# Audio_Output.net
KiCad netlist of a schematic drawn in Altium Designer
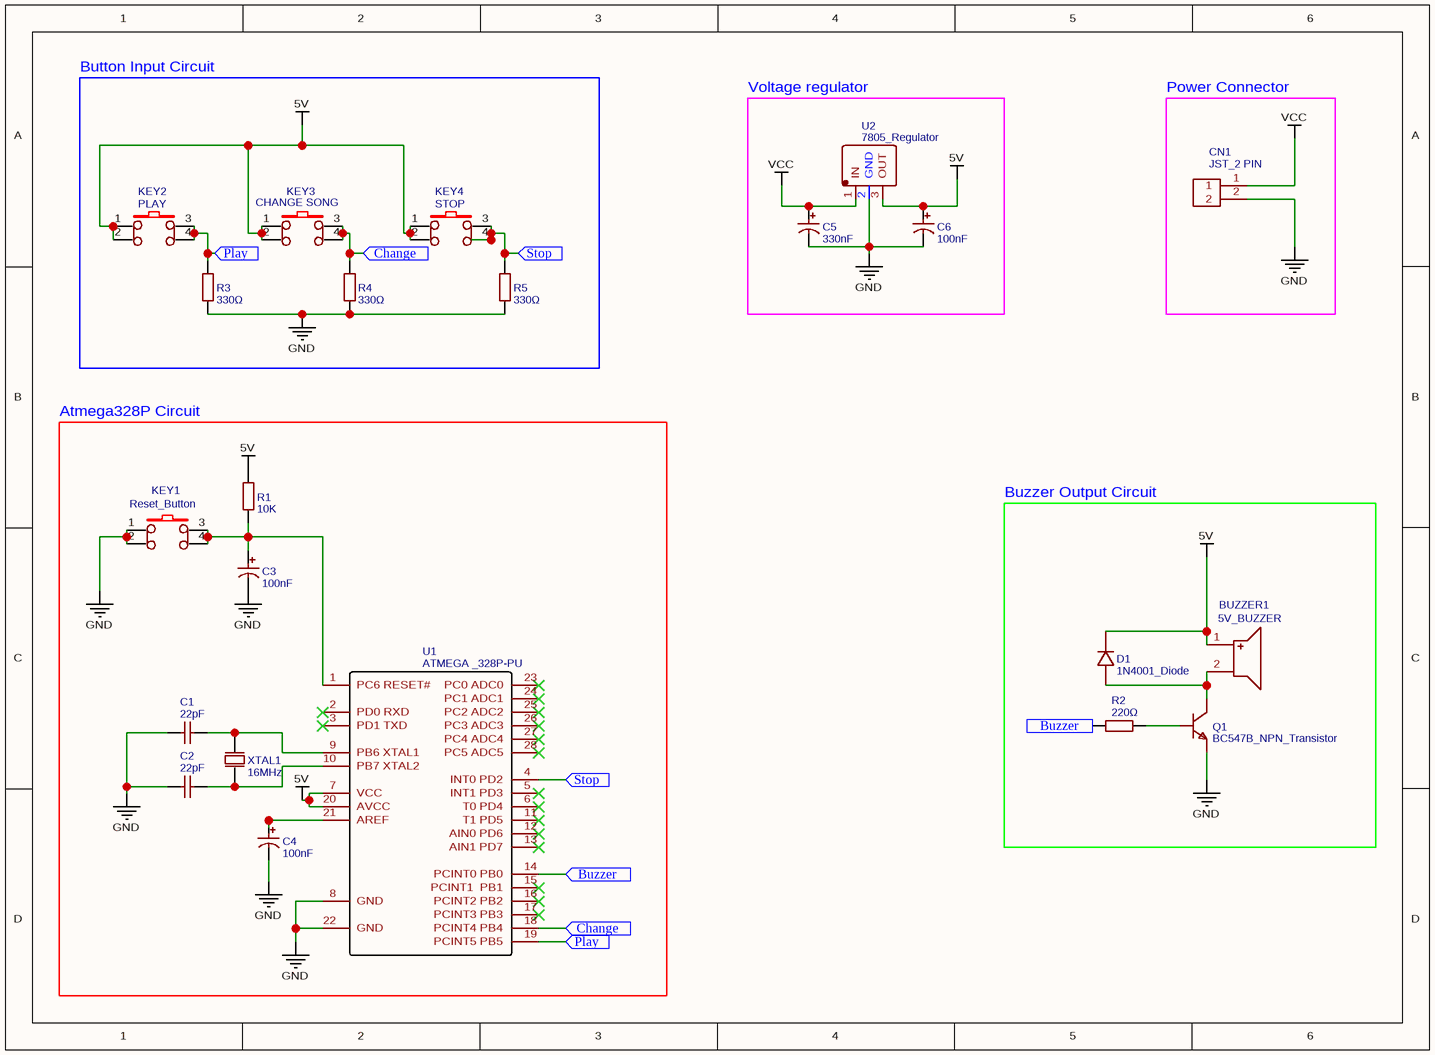
[diagram p0: Audio Output.schdoc]

(export (version "E")
  (design (tool "Eeschema 10.0.6"))
  (components
    (comp (ref "BUZZER1")
      (value "5V_BUZZER")
      (fields
        (field (name "BOM_MANUFACTURER PART") "BUZZERHMB1206-03")
        (field (name "BOM_SUPPLIER PART") "C96101")
        (field (name "CONTRIBUTOR") "วริศรา เกรียงไกรวัฒน์ /ทิพพะ")
      )
      (libsource (lib "altium-import") (part "root_0_5V_BUZZER_"))
    )
    (comp (ref "C1")
      (value "22pF")
      (fields
        (field (name "BOM_MANUFACTURER PART") "22pf/50V 10%")
        (field (name "BOM_SUPPLIER PART") "C9316")
      )
      (libsource (lib "altium-import") (part "root_0_22pF_"))
    )
    (comp (ref "C2")
      (value "22pF")
      (fields
        (field (name "BOM_MANUFACTURER PART") "22pf/50V 10%")
        (field (name "BOM_SUPPLIER PART") "C9316")
      )
      (libsource (lib "altium-import") (part "root_0_22pF_"))
    )
    (comp (ref "C3")
      (value "100nF")
      (fields (field (name "BOM_MANUFACTURER PART") "0.1UF 50V") (field (name "BOM_SUPPLIER PART") "C28061"))
      (libsource (lib "altium-import") (part "root_0_100nF_"))
    )
    (comp (ref "C4")
      (value "100nF")
      (fields (field (name "BOM_MANUFACTURER PART") "0.1UF 50V") (field (name "BOM_SUPPLIER PART") "C28061"))
      (libsource (lib "altium-import") (part "root_0_100nF_"))
    )
    (comp (ref "C5")
      (value "330nF")
      (fields
        (field (name "BOM_MANUFACTURER PART") "0.33uF 50V 5*11")
        (field (name "BOM_SUPPLIER PART") "C45097")
      )
      (libsource (lib "altium-import") (part "root_0_330nF_"))
    )
    (comp (ref "C6")
      (value "100nF")
      (fields (field (name "BOM_MANUFACTURER PART") "0.1UF 50V") (field (name "BOM_SUPPLIER PART") "C28061"))
      (libsource (lib "altium-import") (part "root_0_100nF_"))
    )
    (comp (ref "CN1")
      (value "JST_2 PIN")
      (fields
        (field (name "BOM_MANUFACTURER PART") "XHB-2A Connector")
        (field (name "BOM_SUPPLIER PART") "C57981")
      )
      (libsource (lib "altium-import") (part "root_0_JST_2 PIN_"))
    )
    (comp (ref "D1")
      (value "1N4001_Diode")
      (fields
        (field (name "BOM_SUPPLIER PART") "C99656")
        (field (name "BOM_MANUFACTURER PART") "1N4001-T")
        (field (name "CONTRIBUTOR") "LCSC")
      )
      (libsource (lib "altium-import") (part "root_3_1N4001_Diode_"))
    )
    (comp (ref "KEY1")
      (value "Reset_Button")
      (fields
        (field (name "BOM_SUPPLIER PART") "C59980")
        (field (name "BOM_MANUFACTURER PART") "button6*6*8.5")
      )
      (libsource (lib "altium-import") (part "root_0_Reset_Button_"))
    )
    (comp (ref "KEY2")
      (value "PLAY")
      (fields
        (field (name "BOM_SUPPLIER PART") "C59980")
        (field (name "BOM_MANUFACTURER PART") "button6*6*8.5")
      )
      (libsource (lib "altium-import") (part "root_0_PLAY_"))
    )
    (comp (ref "KEY3")
      (value "CHANGE SONG")
      (fields
        (field (name "BOM_SUPPLIER PART") "C59980")
        (field (name "BOM_MANUFACTURER PART") "button6*6*8.5")
      )
      (libsource (lib "altium-import") (part "root_0_CHANGE SONG_"))
    )
    (comp (ref "KEY4")
      (value "STOP")
      (fields
        (field (name "BOM_SUPPLIER PART") "C59980")
        (field (name "BOM_MANUFACTURER PART") "button6*6*8.5")
      )
      (libsource (lib "altium-import") (part "root_0_STOP_"))
    )
    (comp (ref "Q1")
      (value "BC547B_NPN_Transistor")
      (fields
        (field (name "BOM_SUPPLIER PART") "C713613")
        (field (name "BOM_MANUFACTURER PART") "BC547B")
        (field (name "CONTRIBUTOR") "LCSC")
      )
      (libsource (lib "altium-import") (part "root_0_BC547B_NPN_Transistor_"))
    )
    (comp (ref "R1")
      (value "10K")
      (fields
        (field (name "POWER") "1/4W")
        (field (name "TOLERANCE") "±1%")
        (field (name "BOM_SUPPLIER PART") "E57439")
      )
      (libsource (lib "altium-import") (part "root_1_10K_"))
    )
    (comp (ref "R2")
      (value "220Ω")
      (fields
        (field (name "POWER") "1/4W")
        (field (name "TOLERANCE") "±1%")
        (field (name "BOM_SUPPLIER PART") "E57439")
      )
      (libsource (lib "altium-import") (part "root_0_220Ω_"))
    )
    (comp (ref "R3")
      (value "330Ω")
      (fields
        (field (name "POWER") "1/4W")
        (field (name "TOLERANCE") "±1%")
        (field (name "BOM_SUPPLIER PART") "E57439")
      )
      (libsource (lib "altium-import") (part "root_1_330Ω_"))
    )
    (comp (ref "R4")
      (value "330Ω")
      (fields
        (field (name "POWER") "1/4W")
        (field (name "TOLERANCE") "±1%")
        (field (name "BOM_SUPPLIER PART") "E57439")
      )
      (libsource (lib "altium-import") (part "root_1_330Ω_"))
    )
    (comp (ref "R5")
      (value "330Ω")
      (fields
        (field (name "POWER") "1/4W")
        (field (name "TOLERANCE") "±1%")
        (field (name "BOM_SUPPLIER PART") "E57439")
      )
      (libsource (lib "altium-import") (part "root_1_330Ω_"))
    )
    (comp (ref "U1")
      (value "ATMEGA _328P-PU")
      (fields
        (field (name "BOM_MANUFACTURER PART") "ATMEGA328P-PU")
        (field (name "BOM_SUPPLIER PART") "C33901")
        (field (name "CONTRIBUTOR") "LCSC")
      )
      (libsource (lib "altium-import") (part "root_0_ATMEGA _328P-PU_"))
    )
    (comp (ref "U2")
      (value "7805_Regulator")
      (fields
        (field (name "BOM_SUPPLIER PART") "C305416")
        (field (name "BOM_MANUFACTURER PART") "7805")
        (field (name "CONTRIBUTOR") "LCSC")
      )
      (libsource (lib "altium-import") (part "root_1_7805_Regulator_"))
    )
    (comp (ref "XTAL1")
      (value "16MHz")
      (fields
        (field (name "BOM_MANUFACTURER PART") "0SC-16MHz")
        (field (name "CONTRIBUTOR") "Mantas Petrauskas")
      )
      (libsource (lib "altium-import") (part "root_1_16MHz_"))
    )
  )
  (nets
    (net (code "1") (name "/Buzzer") (class "Default")
      (node (ref "R2") (pin "1") (pinfunction "1_1") (pintype "passive"))
      (node (ref "U1") (pin "14") (pinfunction "PCINT0_PB0_14") (pintype "passive"))
    )
    (net (code "2") (name "/Change") (class "Default")
      (node (ref "KEY3") (pin "3") (pinfunction "3_3") (pintype "passive"))
      (node (ref "KEY3") (pin "4") (pinfunction "4_4") (pintype "passive"))
      (node (ref "R4") (pin "2") (pinfunction "2_2") (pintype "passive"))
      (node (ref "U1") (pin "18") (pinfunction "PCINT4_PB4_18") (pintype "passive"))
    )
    (net (code "3") (name "/Play") (class "Default")
      (node (ref "KEY2") (pin "3") (pinfunction "3_3") (pintype "passive"))
      (node (ref "KEY2") (pin "4") (pinfunction "4_4") (pintype "passive"))
      (node (ref "R3") (pin "2") (pinfunction "2_2") (pintype "passive"))
      (node (ref "U1") (pin "19") (pinfunction "PCINT5_PB5_19") (pintype "passive"))
    )
    (net (code "4") (name "/Stop") (class "Default")
      (node (ref "KEY4") (pin "3") (pinfunction "3_3") (pintype "passive"))
      (node (ref "KEY4") (pin "4") (pinfunction "4_4") (pintype "passive"))
      (node (ref "R5") (pin "2") (pinfunction "2_2") (pintype "passive"))
      (node (ref "U1") (pin "4") (pinfunction "INT0_PD2_4") (pintype "passive"))
    )
    (net (code "5") (name "5V") (class "Default")
      (node (ref "BUZZER1") (pin "1") (pinfunction "1_1") (pintype "passive"))
      (node (ref "C6") (pin "1") (pinfunction "1_1") (pintype "passive"))
      (node (ref "D1") (pin "1") (pinfunction "C_1") (pintype "passive"))
      (node (ref "KEY2") (pin "1") (pinfunction "1_1") (pintype "passive"))
      (node (ref "KEY2") (pin "2") (pinfunction "2_2") (pintype "passive"))
      (node (ref "KEY3") (pin "1") (pinfunction "1_1") (pintype "passive"))
      (node (ref "KEY3") (pin "2") (pinfunction "2_2") (pintype "passive"))
      (node (ref "KEY4") (pin "1") (pinfunction "1_1") (pintype "passive"))
      (node (ref "KEY4") (pin "2") (pinfunction "2_2") (pintype "passive"))
      (node (ref "R1") (pin "2") (pinfunction "2_2") (pintype "passive"))
      (node (ref "U1") (pin "20") (pinfunction "AVCC_20") (pintype "passive"))
      (node (ref "U1") (pin "7") (pinfunction "VCC_7") (pintype "passive"))
      (node (ref "U2") (pin "3") (pinfunction "OUT_3") (pintype "passive"))
    )
    (net (code "6") (name "GND") (class "Default")
      (node (ref "C1") (pin "1") (pinfunction "1_1") (pintype "passive"))
      (node (ref "C2") (pin "1") (pinfunction "1_1") (pintype "passive"))
      (node (ref "C3") (pin "2") (pinfunction "2_2") (pintype "passive"))
      (node (ref "C4") (pin "2") (pinfunction "2_2") (pintype "passive"))
      (node (ref "C5") (pin "2") (pinfunction "2_2") (pintype "passive"))
      (node (ref "C6") (pin "2") (pinfunction "2_2") (pintype "passive"))
      (node (ref "CN1") (pin "2") (pinfunction "2_2") (pintype "passive"))
      (node (ref "KEY1") (pin "1") (pinfunction "1_1") (pintype "passive"))
      (node (ref "KEY1") (pin "2") (pinfunction "2_2") (pintype "passive"))
      (node (ref "Q1") (pin "3") (pinfunction "E_3") (pintype "passive"))
      (node (ref "R3") (pin "1") (pinfunction "1_1") (pintype "passive"))
      (node (ref "R4") (pin "1") (pinfunction "1_1") (pintype "passive"))
      (node (ref "R5") (pin "1") (pinfunction "1_1") (pintype "passive"))
      (node (ref "U1") (pin "22") (pinfunction "GND_22") (pintype "passive"))
      (node (ref "U1") (pin "8") (pinfunction "GND_8") (pintype "passive"))
      (node (ref "U2") (pin "2") (pinfunction "GND_2") (pintype "passive"))
    )
    (net (code "7") (name "Net-(D1-A)") (class "Default")
      (node (ref "BUZZER1") (pin "2") (pinfunction "2_2") (pintype "passive"))
      (node (ref "D1") (pin "2") (pinfunction "A_2") (pintype "passive"))
      (node (ref "Q1") (pin "1") (pinfunction "C_1") (pintype "passive"))
    )
    (net (code "8") (name "Net-(Q1-B)") (class "Default")
      (node (ref "Q1") (pin "2") (pinfunction "B_2") (pintype "passive"))
      (node (ref "R2") (pin "2") (pinfunction "2_2") (pintype "passive"))
    )
    (net (code "9") (name "Net-(U1-AREF)") (class "Default")
      (node (ref "C4") (pin "1") (pinfunction "1_1") (pintype "passive"))
      (node (ref "U1") (pin "21") (pinfunction "AREF_21") (pintype "passive"))
    )
    (net (code "10") (name "Net-(U1-PB6_XTAL1)") (class "Default")
      (node (ref "C1") (pin "2") (pinfunction "2_2") (pintype "passive"))
      (node (ref "U1") (pin "9") (pinfunction "PB6_XTAL1_9") (pintype "passive"))
      (node (ref "XTAL1") (pin "1") (pinfunction "OSC1_1") (pintype "passive"))
    )
    (net (code "11") (name "Net-(U1-PB7_XTAL2)") (class "Default")
      (node (ref "C2") (pin "2") (pinfunction "2_2") (pintype "passive"))
      (node (ref "U1") (pin "10") (pinfunction "PB7_XTAL2_10") (pintype "passive"))
      (node (ref "XTAL1") (pin "2") (pinfunction "OSC2_2") (pintype "passive"))
    )
    (net (code "12") (name "Net-(U1-PC6_RESET#)") (class "Default")
      (node (ref "C3") (pin "1") (pinfunction "1_1") (pintype "passive"))
      (node (ref "KEY1") (pin "3") (pinfunction "3_3") (pintype "passive"))
      (node (ref "KEY1") (pin "4") (pinfunction "4_4") (pintype "passive"))
      (node (ref "R1") (pin "1") (pinfunction "1_1") (pintype "passive"))
      (node (ref "U1") (pin "1") (pinfunction "PC6_RESET#_1") (pintype "passive"))
    )
    (net (code "13") (name "VCC") (class "Default")
      (node (ref "C5") (pin "1") (pinfunction "1_1") (pintype "passive"))
      (node (ref "CN1") (pin "1") (pinfunction "1_1") (pintype "passive"))
      (node (ref "U2") (pin "1") (pinfunction "IN_1") (pintype "passive"))
    )
    (net (code "14") (name "unconnected-(U1-AIN0_PD6-Pad12)") (class "Default")
      (node (ref "U1") (pin "12") (pinfunction "AIN0_PD6_12") (pintype "passive+no_connect"))
    )
    (net (code "15") (name "unconnected-(U1-AIN1_PD7-Pad13)") (class "Default")
      (node (ref "U1") (pin "13") (pinfunction "AIN1_PD7_13") (pintype "passive+no_connect"))
    )
    (net (code "16") (name "unconnected-(U1-INT1_PD3-Pad5)") (class "Default")
      (node (ref "U1") (pin "5") (pinfunction "INT1_PD3_5") (pintype "passive+no_connect"))
    )
    (net (code "17") (name "unconnected-(U1-PC0_ADC0-Pad23)") (class "Default")
      (node (ref "U1") (pin "23") (pinfunction "PC0_ADC0_23") (pintype "passive+no_connect"))
    )
    (net (code "18") (name "unconnected-(U1-PC1_ADC1-Pad24)") (class "Default")
      (node (ref "U1") (pin "24") (pinfunction "PC1_ADC1_24") (pintype "passive+no_connect"))
    )
    (net (code "19") (name "unconnected-(U1-PC2_ADC2-Pad25)") (class "Default")
      (node (ref "U1") (pin "25") (pinfunction "PC2_ADC2_25") (pintype "passive+no_connect"))
    )
    (net (code "20") (name "unconnected-(U1-PC3_ADC3-Pad26)") (class "Default")
      (node (ref "U1") (pin "26") (pinfunction "PC3_ADC3_26") (pintype "passive+no_connect"))
    )
    (net (code "21") (name "unconnected-(U1-PC4_ADC4-Pad27)") (class "Default")
      (node (ref "U1") (pin "27") (pinfunction "PC4_ADC4_27") (pintype "passive+no_connect"))
    )
    (net (code "22") (name "unconnected-(U1-PC5_ADC5-Pad28)") (class "Default")
      (node (ref "U1") (pin "28") (pinfunction "PC5_ADC5_28") (pintype "passive+no_connect"))
    )
    (net (code "23") (name "unconnected-(U1-PCINT1__PB1-Pad15)") (class "Default")
      (node (ref "U1") (pin "15") (pinfunction "PCINT1__PB1_15") (pintype "passive+no_connect"))
    )
    (net (code "24") (name "unconnected-(U1-PCINT2_PB2-Pad16)") (class "Default")
      (node (ref "U1") (pin "16") (pinfunction "PCINT2_PB2_16") (pintype "passive+no_connect"))
    )
    (net (code "25") (name "unconnected-(U1-PCINT3_PB3-Pad17)") (class "Default")
      (node (ref "U1") (pin "17") (pinfunction "PCINT3_PB3_17") (pintype "passive+no_connect"))
    )
    (net (code "26") (name "unconnected-(U1-PD0_RXD-Pad2)") (class "Default")
      (node (ref "U1") (pin "2") (pinfunction "PD0_RXD_2") (pintype "passive+no_connect"))
    )
    (net (code "27") (name "unconnected-(U1-PD1_TXD-Pad3)") (class "Default")
      (node (ref "U1") (pin "3") (pinfunction "PD1_TXD_3") (pintype "passive+no_connect"))
    )
    (net (code "28") (name "unconnected-(U1-T0_PD4-Pad6)") (class "Default")
      (node (ref "U1") (pin "6") (pinfunction "T0_PD4_6") (pintype "passive+no_connect"))
    )
    (net (code "29") (name "unconnected-(U1-T1_PD5-Pad11)") (class "Default")
      (node (ref "U1") (pin "11") (pinfunction "T1_PD5_11") (pintype "passive+no_connect"))
    )
  )
)
